# SCH_NFC-Buisness-card_2026-05-22.net
KiCad netlist of a schematic drawn in EasyEDA
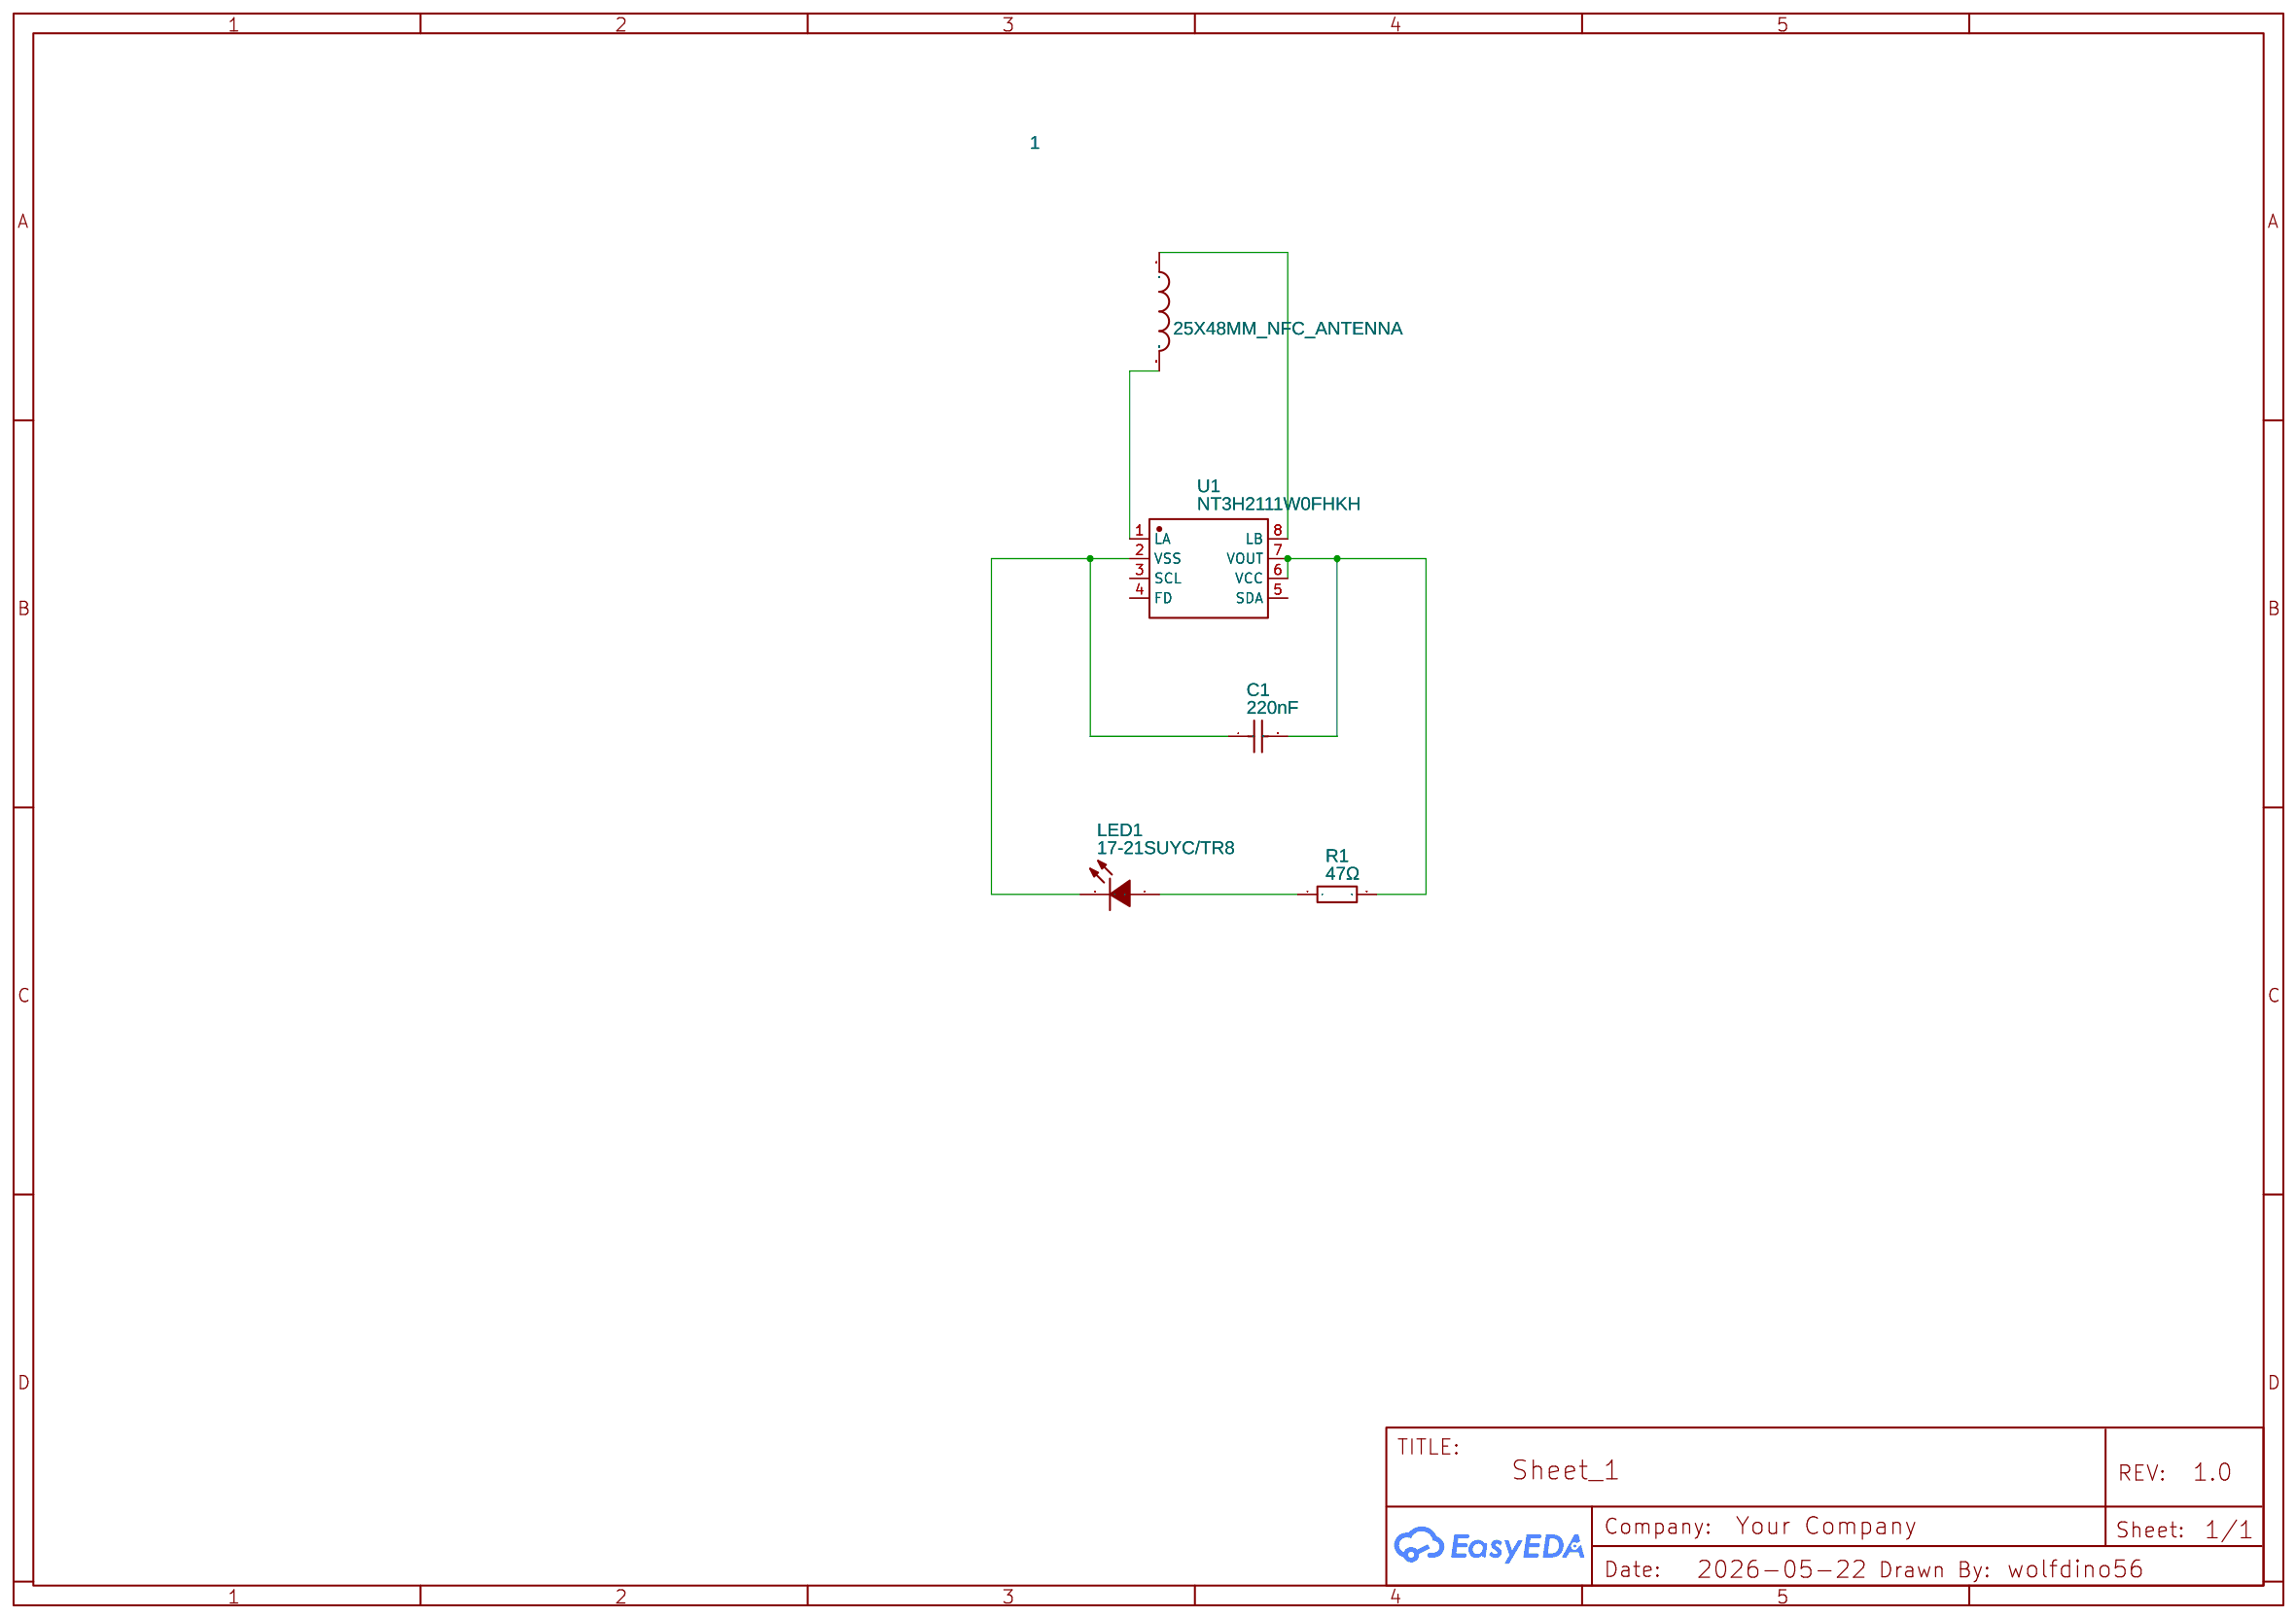
[diagram p0: schematic sheet]

(export (version "E")
  (design (tool "Eeschema 10.0.6"))
  (components
    (comp (ref "1") (value "25X48MM_NFC_ANTENNA") (libsource (lib "") (part "25X48MM_NFC_ANTENNA")))
    (comp (ref "C1")
      (value "220nF")
      (fields
        (field (name "Manufacturer Part") "CL10B224KA8NNNC")
        (field (name "Manufacturer") "SAMSUNG(三星)")
      )
      (libsource (lib "") (part "CL10B224KA8NNNC"))
    )
    (comp (ref "LED1")
      (value "17-21SUYC/TR8")
      (fields (field (name "Manufacturer Part") "KT-0805黄灯") (field (name "Manufacturer") "KENTO"))
      (libsource (lib "") (part "17-21SUYC/TR8"))
    )
    (comp (ref "R1")
      (value "47Ω")
      (fields
        (field (name "Manufacturer Part") "0603WAF470JT5E")
        (field (name "Manufacturer") "UNI-ROYAL(厚声)")
      )
      (libsource (lib "") (part "0603WAF470JT5E"))
    )
    (comp (ref "U1")
      (value "NT3H2111W0FHKH")
      (fields (field (name "Manufacturer") "NXP(恩智浦)"))
      (libsource (lib "") (part "NT3H2111W0FHKH"))
    )
  )
  (nets
    (net (code "1") (name "Net-(LED1-+)") (class "Default")
      (node (ref "LED1") (pin "1") (pinfunction "+_1") (pintype "unspecified"))
      (node (ref "R1") (pin "1") (pinfunction "1_1") (pintype "input"))
    )
    (net (code "2") (name "Net-(LED1--)") (class "Default")
      (node (ref "C1") (pin "1") (pinfunction "1_1") (pintype "input"))
      (node (ref "LED1") (pin "2") (pinfunction "-_2") (pintype "unspecified"))
      (node (ref "U1") (pin "2") (pinfunction "VSS_2") (pintype "unspecified"))
    )
    (net (code "3") (name "Net-(U1-LA)") (class "Default")
      (node (ref "1") (pin "P$2") (pinfunction "P$2_P$2") (pintype "bidirectional"))
      (node (ref "U1") (pin "1") (pinfunction "LA_1") (pintype "unspecified"))
    )
    (net (code "4") (name "Net-(U1-LB)") (class "Default")
      (node (ref "1") (pin "P$1") (pinfunction "P$1_P$1") (pintype "bidirectional"))
      (node (ref "U1") (pin "8") (pinfunction "LB_8") (pintype "unspecified"))
    )
    (net (code "5") (name "Net-(U1-VCC)") (class "Default")
      (node (ref "C1") (pin "2") (pinfunction "2_2") (pintype "input"))
      (node (ref "R1") (pin "2") (pinfunction "2_2") (pintype "input"))
      (node (ref "U1") (pin "6") (pinfunction "VCC_6") (pintype "unspecified"))
      (node (ref "U1") (pin "7") (pinfunction "VOUT_7") (pintype "unspecified"))
    )
    (net (code "6") (name "unconnected-(U1-FD-Pad4)") (class "Default")
      (node (ref "U1") (pin "4") (pinfunction "FD_4") (pintype "unspecified"))
    )
    (net (code "7") (name "unconnected-(U1-SCL-Pad3)") (class "Default")
      (node (ref "U1") (pin "3") (pinfunction "SCL_3") (pintype "unspecified"))
    )
    (net (code "8") (name "unconnected-(U1-SDA-Pad5)") (class "Default")
      (node (ref "U1") (pin "5") (pinfunction "SDA_5") (pintype "unspecified"))
    )
  )
)
